# VC8Evrs2.net
KiCad netlist of a schematic drawn in EAGLE
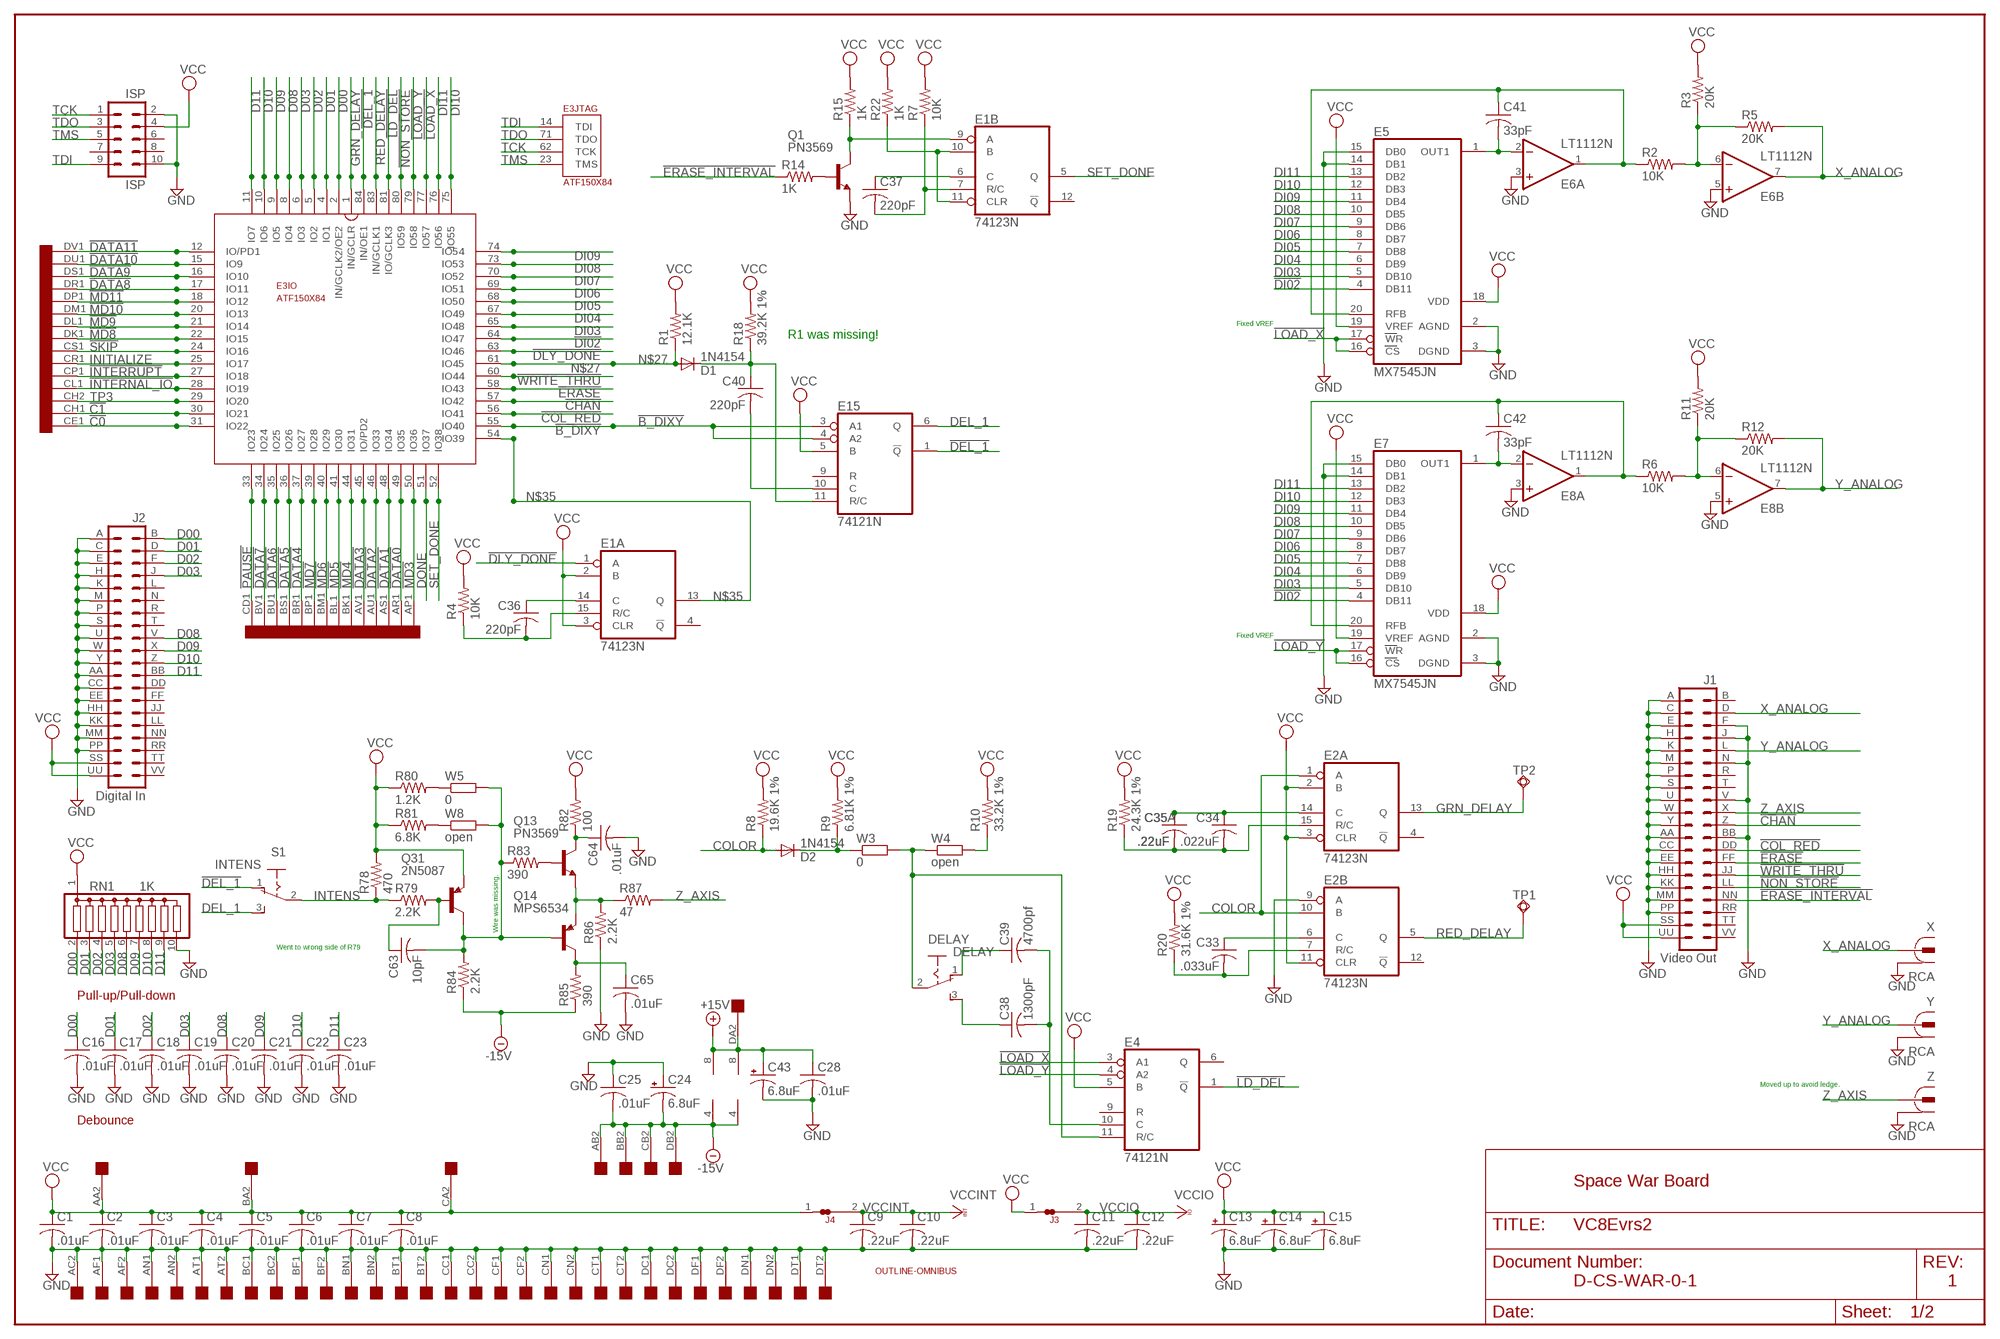
[diagram p0: schematic, sheet 1]

(export (version "E")
  (design (tool "Eeschema 10.0.6"))
  (components
    (comp (ref "C1")
      (value ".01uF")
      (footprint "eagle-import:C063-025X075")
      (libsource (lib "eagle-import") (part "C-US"))
    )
    (comp (ref "C2")
      (value ".01uF")
      (footprint "eagle-import:C063-025X075")
      (libsource (lib "eagle-import") (part "C-US"))
    )
    (comp (ref "C3")
      (value ".01uF")
      (footprint "eagle-import:C063-025X075")
      (libsource (lib "eagle-import") (part "C-US"))
    )
    (comp (ref "C4")
      (value ".01uF")
      (footprint "eagle-import:C063-025X075")
      (libsource (lib "eagle-import") (part "C-US"))
    )
    (comp (ref "C5")
      (value ".01uF")
      (footprint "eagle-import:C063-025X075")
      (libsource (lib "eagle-import") (part "C-US"))
    )
    (comp (ref "C6")
      (value ".01uF")
      (footprint "eagle-import:C063-025X075")
      (libsource (lib "eagle-import") (part "C-US"))
    )
    (comp (ref "C7")
      (value ".01uF")
      (footprint "eagle-import:C063-025X075")
      (libsource (lib "eagle-import") (part "C-US"))
    )
    (comp (ref "C8")
      (value ".01uF")
      (footprint "eagle-import:C063-025X075")
      (libsource (lib "eagle-import") (part "C-US"))
    )
    (comp (ref "C9")
      (value ".22uF")
      (footprint "eagle-import:C063-025X075")
      (libsource (lib "eagle-import") (part "C-US"))
    )
    (comp (ref "C10")
      (value ".22uF")
      (footprint "eagle-import:C063-025X075")
      (libsource (lib "eagle-import") (part "C-US"))
    )
    (comp (ref "C11")
      (value ".22uF")
      (footprint "eagle-import:C063-025X075")
      (libsource (lib "eagle-import") (part "C-US"))
    )
    (comp (ref "C12")
      (value ".22uF")
      (footprint "eagle-import:C063-025X075")
      (libsource (lib "eagle-import") (part "C-US"))
    )
    (comp (ref "C13")
      (value "6.8uF")
      (footprint "eagle-import:E12-8")
      (libsource (lib "eagle-import") (part "CPOL-USE20-8AXIAL"))
    )
    (comp (ref "C14")
      (value "6.8uF")
      (footprint "eagle-import:E12-8")
      (libsource (lib "eagle-import") (part "CPOL-USE20-8AXIAL"))
    )
    (comp (ref "C15")
      (value "6.8uF")
      (footprint "eagle-import:E12-8")
      (libsource (lib "eagle-import") (part "CPOL-USE20-8AXIAL"))
    )
    (comp (ref "C16")
      (value ".01uF")
      (footprint "eagle-import:C063-025X075")
      (libsource (lib "eagle-import") (part "C-US"))
    )
    (comp (ref "C17")
      (value ".01uF")
      (footprint "eagle-import:C063-025X075")
      (libsource (lib "eagle-import") (part "C-US"))
    )
    (comp (ref "C18")
      (value ".01uF")
      (footprint "eagle-import:C063-025X075")
      (libsource (lib "eagle-import") (part "C-US"))
    )
    (comp (ref "C19")
      (value ".01uF")
      (footprint "eagle-import:C063-025X075")
      (libsource (lib "eagle-import") (part "C-US"))
    )
    (comp (ref "C20")
      (value ".01uF")
      (footprint "eagle-import:C063-025X075")
      (libsource (lib "eagle-import") (part "C-US"))
    )
    (comp (ref "C21")
      (value ".01uF")
      (footprint "eagle-import:C063-025X075")
      (libsource (lib "eagle-import") (part "C-US"))
    )
    (comp (ref "C22")
      (value ".01uF")
      (footprint "eagle-import:C063-025X075")
      (libsource (lib "eagle-import") (part "C-US"))
    )
    (comp (ref "C23")
      (value ".01uF")
      (footprint "eagle-import:C063-025X075")
      (libsource (lib "eagle-import") (part "C-US"))
    )
    (comp (ref "C24")
      (value "6.8uF")
      (footprint "eagle-import:E12-8")
      (libsource (lib "eagle-import") (part "CPOL-USE20-8AXIAL"))
    )
    (comp (ref "C25")
      (value ".01uF")
      (footprint "eagle-import:C063-025X075")
      (libsource (lib "eagle-import") (part "C-US"))
    )
    (comp (ref "C28")
      (value ".01uF")
      (footprint "eagle-import:C063-025X075")
      (libsource (lib "eagle-import") (part "C-US"))
    )
    (comp (ref "C33")
      (value ".033uF")
      (footprint "eagle-import:C102-043X133")
      (libsource (lib "eagle-import") (part "C-US102-043X133"))
    )
    (comp (ref "C34")
      (value ".022uF")
      (footprint "eagle-import:C102-043X133")
      (libsource (lib "eagle-import") (part "C-US102-043X133"))
    )
    (comp (ref "C35")
      (value ".22uF")
      (footprint "eagle-import:C050-025X075")
      (libsource (lib "eagle-import") (part "C-US050-025X075"))
    )
    (comp (ref "C35A")
      (value ".22uF")
      (footprint "eagle-import:C102-043X133")
      (libsource (lib "eagle-import") (part "C-US102-043X133"))
    )
    (comp (ref "C36")
      (value "220pF")
      (footprint "eagle-import:C063-025X075")
      (libsource (lib "eagle-import") (part "C-US"))
    )
    (comp (ref "C37")
      (value "220pF")
      (footprint "eagle-import:C063-025X075")
      (libsource (lib "eagle-import") (part "C-US"))
    )
    (comp (ref "C38")
      (value "1300pF")
      (footprint "eagle-import:C150-054X183")
      (libsource (lib "eagle-import") (part "C-US150-054X183"))
    )
    (comp (ref "C39")
      (value "4700pf")
      (footprint "eagle-import:C102-043X133")
      (libsource (lib "eagle-import") (part "C-US102-043X133"))
    )
    (comp (ref "C40")
      (value "220pF")
      (footprint "eagle-import:C063-025X075")
      (libsource (lib "eagle-import") (part "C-US"))
    )
    (comp (ref "C41")
      (value "33pF")
      (footprint "eagle-import:C063-025X075")
      (libsource (lib "eagle-import") (part "C-US"))
    )
    (comp (ref "C42")
      (value "33pF")
      (footprint "eagle-import:C063-025X075")
      (libsource (lib "eagle-import") (part "C-US"))
    )
    (comp (ref "C43")
      (value "6.8uF")
      (footprint "eagle-import:E12-8")
      (libsource (lib "eagle-import") (part "CPOL-USE20-8AXIAL"))
    )
    (comp (ref "C63")
      (value "10pF")
      (footprint "eagle-import:C063-025X075")
      (libsource (lib "eagle-import") (part "C-US"))
    )
    (comp (ref "C64")
      (value ".01uF")
      (footprint "eagle-import:C063-025X075")
      (libsource (lib "eagle-import") (part "C-US"))
    )
    (comp (ref "C65")
      (value ".01uF")
      (footprint "eagle-import:C063-025X075")
      (libsource (lib "eagle-import") (part "C-US"))
    )
    (comp (ref "D1")
      (value "1N4154")
      (footprint "eagle-import:DO35-10")
      (libsource (lib "eagle-import") (part "DIODE-DO35-10"))
    )
    (comp (ref "D2")
      (value "1N4154")
      (footprint "eagle-import:DO35-10")
      (libsource (lib "eagle-import") (part "DIODE-DO35-10"))
    )
    (comp (ref "DELAY")
      (value "DELAY")
      (footprint "eagle-import:M251")
      (libsource (lib "eagle-import") (part "M251"))
    )
    (comp (ref "E1")
      (value "74123N")
      (footprint "eagle-import:DIL16")
      (libsource (lib "eagle-import") (part "74123N"))
    )
    (comp (ref "E2")
      (value "74123N")
      (footprint "eagle-import:DIL16")
      (libsource (lib "eagle-import") (part "74123N"))
    )
    (comp (ref "E3")
      (value "ATF150X84")
      (footprint "eagle-import:S84")
      (libsource (lib "eagle-import") (part "ATF150X84"))
    )
    (comp (ref "E4")
      (value "74121N")
      (footprint "eagle-import:DIL14")
      (libsource (lib "eagle-import") (part "74121N"))
    )
    (comp (ref "E5")
      (value "MX7545JN")
      (footprint "eagle-import:DIL20")
      (fields (field (name "MPN") "MX7545JN+"))
      (libsource (lib "eagle-import") (part "MX7545JN"))
    )
    (comp (ref "E6")
      (value "LT1112N")
      (footprint "eagle-import:DIL08")
      (libsource (lib "eagle-import") (part "1458NLM"))
    )
    (comp (ref "E7")
      (value "MX7545JN")
      (footprint "eagle-import:DIL20")
      (fields (field (name "MPN") "MX7545JN+"))
      (libsource (lib "eagle-import") (part "MX7545JN"))
    )
    (comp (ref "E8")
      (value "LT1112N")
      (footprint "eagle-import:DIL08")
      (libsource (lib "eagle-import") (part "1458NLM"))
    )
    (comp (ref "E15")
      (value "74121N")
      (footprint "eagle-import:DIL14")
      (libsource (lib "eagle-import") (part "74121N"))
    )
    (comp (ref "ISP")
      (value "ISP")
      (footprint "eagle-import:ML10")
      (libsource (lib "eagle-import") (part "ML10"))
    )
    (comp (ref "J1")
      (value "Video Out")
      (footprint "eagle-import:DEC40PINH")
      (libsource (lib "eagle-import") (part "DEC40PINH"))
    )
    (comp (ref "J2")
      (value "Digital In")
      (footprint "eagle-import:DEC40PINH")
      (libsource (lib "eagle-import") (part "DEC40PINH"))
    )
    (comp (ref "J3")
      (value "JUMPER-NC1")
      (footprint "eagle-import:NC1")
      (libsource (lib "eagle-import") (part "JUMPER-NC1"))
    )
    (comp (ref "J4")
      (value "JUMPER-NC1")
      (footprint "eagle-import:NC1")
      (libsource (lib "eagle-import") (part "JUMPER-NC1"))
    )
    (comp (ref "OMNIBUS")
      (value "QUAD")
      (footprint "eagle-import:EDGE-CON8")
      (libsource (lib "eagle-import") (part "QUAD"))
    )
    (comp (ref "Q1")
      (value "PN3569")
      (footprint "eagle-import:TO5")
      (libsource (lib "eagle-import") (part "-NPN-TO5"))
    )
    (comp (ref "Q13")
      (value "PN3569")
      (footprint "eagle-import:TO5")
      (libsource (lib "eagle-import") (part "-NPN-TO5"))
    )
    (comp (ref "Q14")
      (value "MPS6534")
      (footprint "eagle-import:TO5")
      (libsource (lib "eagle-import") (part "-PNP-TO5"))
    )
    (comp (ref "Q31")
      (value "2N5087")
      (footprint "eagle-import:TO5")
      (libsource (lib "eagle-import") (part "-PNP-TO5"))
    )
    (comp (ref "R1")
      (value "12.1K")
      (footprint "eagle-import:0207_15")
      (libsource (lib "eagle-import") (part "R-US_0207/15"))
    )
    (comp (ref "R2")
      (value "10K")
      (footprint "eagle-import:0207_10")
      (libsource (lib "eagle-import") (part "R-US_0207/10"))
    )
    (comp (ref "R3")
      (value "20K")
      (footprint "eagle-import:0207_10")
      (libsource (lib "eagle-import") (part "R-US_0207/10"))
    )
    (comp (ref "R4")
      (value "10K")
      (footprint "eagle-import:0207_10")
      (libsource (lib "eagle-import") (part "R-US_0207/10"))
    )
    (comp (ref "R5")
      (value "20K")
      (footprint "eagle-import:0207_10")
      (libsource (lib "eagle-import") (part "R-US_0207/10"))
    )
    (comp (ref "R6")
      (value "10K")
      (footprint "eagle-import:0207_10")
      (libsource (lib "eagle-import") (part "R-US_0207/10"))
    )
    (comp (ref "R7")
      (value "10K")
      (footprint "eagle-import:0207_10")
      (libsource (lib "eagle-import") (part "R-US_0207/10"))
    )
    (comp (ref "R8")
      (value "19.6K 1%")
      (footprint "eagle-import:0207_15")
      (libsource (lib "eagle-import") (part "R-US_0207/15"))
    )
    (comp (ref "R9")
      (value "6.81K 1%")
      (footprint "eagle-import:0207_15")
      (libsource (lib "eagle-import") (part "R-US_0207/15"))
    )
    (comp (ref "R10")
      (value "33.2K 1%")
      (footprint "eagle-import:0207_15")
      (libsource (lib "eagle-import") (part "R-US_0207/15"))
    )
    (comp (ref "R11")
      (value "20K")
      (footprint "eagle-import:0207_10")
      (libsource (lib "eagle-import") (part "R-US_0207/10"))
    )
    (comp (ref "R12")
      (value "20K")
      (footprint "eagle-import:0207_10")
      (libsource (lib "eagle-import") (part "R-US_0207/10"))
    )
    (comp (ref "R14")
      (value "1K")
      (footprint "eagle-import:0207_10")
      (libsource (lib "eagle-import") (part "R-US_0207/10"))
    )
    (comp (ref "R15")
      (value "1K")
      (footprint "eagle-import:0207_10")
      (libsource (lib "eagle-import") (part "R-US_0207/10"))
    )
    (comp (ref "R18")
      (value "39.2K 1%")
      (footprint "eagle-import:0207_15")
      (libsource (lib "eagle-import") (part "R-US_0207/15"))
    )
    (comp (ref "R19")
      (value "24.3K 1%")
      (footprint "eagle-import:0207_15")
      (libsource (lib "eagle-import") (part "R-US_0207/15"))
    )
    (comp (ref "R20")
      (value "31.6K 1%")
      (footprint "eagle-import:0207_15")
      (libsource (lib "eagle-import") (part "R-US_0207/15"))
    )
    (comp (ref "R22")
      (value "1K")
      (footprint "eagle-import:0207_10")
      (libsource (lib "eagle-import") (part "R-US_0207/10"))
    )
    (comp (ref "R78")
      (value "470")
      (footprint "eagle-import:0207_10")
      (libsource (lib "eagle-import") (part "R-US_0207/10"))
    )
    (comp (ref "R79")
      (value "2.2K")
      (footprint "eagle-import:0207_10")
      (libsource (lib "eagle-import") (part "R-US_0207/10"))
    )
    (comp (ref "R80")
      (value "1.2K")
      (footprint "eagle-import:0207_10")
      (libsource (lib "eagle-import") (part "R-US_0207/10"))
    )
    (comp (ref "R81")
      (value "6.8K")
      (footprint "eagle-import:0207_10")
      (libsource (lib "eagle-import") (part "R-US_0207/10"))
    )
    (comp (ref "R82")
      (value "100")
      (footprint "eagle-import:0207_10")
      (libsource (lib "eagle-import") (part "R-US_0207/10"))
    )
    (comp (ref "R83")
      (value "390")
      (footprint "eagle-import:0207_10")
      (libsource (lib "eagle-import") (part "R-US_0207/10"))
    )
    (comp (ref "R84")
      (value "2.2K")
      (footprint "eagle-import:0207_10")
      (libsource (lib "eagle-import") (part "R-US_0207/10"))
    )
    (comp (ref "R85")
      (value "390")
      (footprint "eagle-import:0207_10")
      (libsource (lib "eagle-import") (part "R-US_0207/10"))
    )
    (comp (ref "R86")
      (value "2.2K")
      (footprint "eagle-import:0207_10")
      (libsource (lib "eagle-import") (part "R-US_0207/10"))
    )
    (comp (ref "R87")
      (value "47")
      (footprint "eagle-import:0207_10")
      (libsource (lib "eagle-import") (part "R-US_0207/10"))
    )
    (comp (ref "RN1")
      (value "1K")
      (footprint "eagle-import:SIL10")
      (libsource (lib "eagle-import") (part "G09R"))
    )
    (comp (ref "S1")
      (value "INTENS")
      (footprint "eagle-import:M251")
      (libsource (lib "eagle-import") (part "M251"))
    )
    (comp (ref "TP1")
      (value "TPSQPAD1-17")
      (footprint "eagle-import:P1-17")
      (libsource (lib "eagle-import") (part "TPSQPAD1-17"))
    )
    (comp (ref "TP2")
      (value "TPSQPAD1-17")
      (footprint "eagle-import:P1-17")
      (libsource (lib "eagle-import") (part "TPSQPAD1-17"))
    )
    (comp (ref "U$1")
      (value "OUTLINE-OMNIBUS")
      (footprint "eagle-import:OMNIBUS")
      (libsource (lib "eagle-import") (part "OUTLINE-OMNIBUS"))
    )
    (comp (ref "W3")
      (value "0")
      (footprint "eagle-import:0207_10")
      (libsource (lib "eagle-import") (part "R-EU_0207/10"))
    )
    (comp (ref "W4")
      (value "open")
      (footprint "eagle-import:0207_10")
      (libsource (lib "eagle-import") (part "R-EU_0207/10"))
    )
    (comp (ref "W5")
      (value "0")
      (footprint "eagle-import:0207_10")
      (libsource (lib "eagle-import") (part "R-EU_0207/10"))
    )
    (comp (ref "W8")
      (value "open")
      (footprint "eagle-import:0207_10")
      (libsource (lib "eagle-import") (part "R-EU_0207/10"))
    )
    (comp (ref "X")
      (value "RCA")
      (footprint "eagle-import:RCA")
      (libsource (lib "eagle-import") (part "RCA"))
    )
    (comp (ref "Y")
      (value "RCA")
      (footprint "eagle-import:RCA")
      (libsource (lib "eagle-import") (part "RCA"))
    )
    (comp (ref "Z")
      (value "RCA")
      (footprint "eagle-import:RCA")
      (libsource (lib "eagle-import") (part "RCA"))
    )
  )
  (nets
    (net (code "1") (name "+15V") (class "Default")
      (node (ref "C28") (pin "1") (pinfunction "1_1") (pintype "passive"))
      (node (ref "C43") (pin "+") (pinfunction "+_+") (pintype "passive"))
      (node (ref "E6") (pin "8") (pinfunction "V+_8") (pintype "power_in"))
      (node (ref "E8") (pin "8") (pinfunction "V+_8") (pintype "power_in"))
      (node (ref "OMNIBUS") (pin "DA2") (pinfunction "1_DA2") (pintype "bidirectional"))
    )
    (net (code "2") (name "-15V") (class "Default")
      (node (ref "C24") (pin "-") (pinfunction "-_-") (pintype "passive"))
      (node (ref "C25") (pin "2") (pinfunction "2_2") (pintype "passive"))
      (node (ref "E6") (pin "4") (pinfunction "V-_4") (pintype "power_in"))
      (node (ref "E8") (pin "4") (pinfunction "V-_4") (pintype "power_in"))
      (node (ref "OMNIBUS") (pin "AB2") (pinfunction "1_AB2") (pintype "bidirectional"))
      (node (ref "OMNIBUS") (pin "BB2") (pinfunction "1_BB2") (pintype "bidirectional"))
      (node (ref "OMNIBUS") (pin "CB2") (pinfunction "1_CB2") (pintype "bidirectional"))
      (node (ref "OMNIBUS") (pin "DB2") (pinfunction "1_DB2") (pintype "bidirectional"))
      (node (ref "R84") (pin "1") (pinfunction "1_1") (pintype "passive"))
      (node (ref "R85") (pin "1") (pinfunction "1_1") (pintype "passive"))
    )
    (net (code "3") (name "COLOR") (class "Default")
      (node (ref "D2") (pin "A") (pinfunction "A_A") (pintype "passive"))
      (node (ref "E2") (pin "1") (pinfunction "A_1") (pintype "input"))
      (node (ref "E2") (pin "10") (pinfunction "B_10") (pintype "input"))
      (node (ref "R8") (pin "1") (pinfunction "1_1") (pintype "passive"))
    )
    (net (code "4") (name "D00") (class "Default")
      (node (ref "C16") (pin "1") (pinfunction "1_1") (pintype "passive"))
      (node (ref "E3") (pin "2") (pinfunction "IN/GCLK2/OE2_2") (pintype "input"))
      (node (ref "J2") (pin "B") (pinfunction "2_B") (pintype "bidirectional"))
      (node (ref "RN1") (pin "2") (pinfunction "2_2") (pintype "passive"))
    )
    (net (code "5") (name "D01") (class "Default")
      (node (ref "C17") (pin "1") (pinfunction "1_1") (pintype "passive"))
      (node (ref "E3") (pin "4") (pinfunction "IO1_4") (pintype "bidirectional"))
      (node (ref "J2") (pin "D") (pinfunction "4_D") (pintype "bidirectional"))
      (node (ref "RN1") (pin "3") (pinfunction "3_3") (pintype "passive"))
    )
    (net (code "6") (name "D02") (class "Default")
      (node (ref "C18") (pin "1") (pinfunction "1_1") (pintype "passive"))
      (node (ref "E3") (pin "5") (pinfunction "IO2_5") (pintype "bidirectional"))
      (node (ref "J2") (pin "F") (pinfunction "6_F") (pintype "bidirectional"))
      (node (ref "RN1") (pin "4") (pinfunction "4_4") (pintype "passive"))
    )
    (net (code "7") (name "D03") (class "Default")
      (node (ref "C19") (pin "1") (pinfunction "1_1") (pintype "passive"))
      (node (ref "E3") (pin "6") (pinfunction "IO3_6") (pintype "bidirectional"))
      (node (ref "J2") (pin "J") (pinfunction "8_J") (pintype "bidirectional"))
      (node (ref "RN1") (pin "5") (pinfunction "5_5") (pintype "passive"))
    )
    (net (code "8") (name "D08") (class "Default")
      (node (ref "C20") (pin "1") (pinfunction "1_1") (pintype "passive"))
      (node (ref "E3") (pin "8") (pinfunction "IO4_8") (pintype "bidirectional"))
      (node (ref "J2") (pin "V") (pinfunction "18_V") (pintype "bidirectional"))
      (node (ref "RN1") (pin "6") (pinfunction "6_6") (pintype "passive"))
    )
    (net (code "9") (name "D09") (class "Default")
      (node (ref "C21") (pin "1") (pinfunction "1_1") (pintype "passive"))
      (node (ref "E3") (pin "9") (pinfunction "IO5_9") (pintype "bidirectional"))
      (node (ref "J2") (pin "X") (pinfunction "20_X") (pintype "bidirectional"))
      (node (ref "RN1") (pin "7") (pinfunction "7_7") (pintype "passive"))
    )
    (net (code "10") (name "D10") (class "Default")
      (node (ref "C22") (pin "1") (pinfunction "1_1") (pintype "passive"))
      (node (ref "E3") (pin "10") (pinfunction "IO6_10") (pintype "bidirectional"))
      (node (ref "J2") (pin "Z") (pinfunction "22_Z") (pintype "bidirectional"))
      (node (ref "RN1") (pin "8") (pinfunction "8_8") (pintype "passive"))
    )
    (net (code "11") (name "D11") (class "Default")
      (node (ref "C23") (pin "1") (pinfunction "1_1") (pintype "passive"))
      (node (ref "E3") (pin "11") (pinfunction "IO7_11") (pintype "bidirectional"))
      (node (ref "J2") (pin "BB") (pinfunction "24_BB") (pintype "bidirectional"))
      (node (ref "RN1") (pin "9") (pinfunction "9_9") (pintype "passive"))
    )
    (net (code "12") (name "DEL_1") (class "Default")
      (node (ref "E15") (pin "6") (pinfunction "Q_6") (pintype "output"))
      (node (ref "S1") (pin "3") (pinfunction "S_3") (pintype "passive"))
    )
    (net (code "13") (name "DI03") (class "Default")
      (node (ref "E3") (pin "65") (pinfunction "IO48_65") (pintype "bidirectional"))
      (node (ref "E5") (pin "5") (pinfunction "DB10_5") (pintype "input"))
      (node (ref "E7") (pin "5") (pinfunction "DB10_5") (pintype "input"))
    )
    (net (code "14") (name "DI04") (class "Default")
      (node (ref "E3") (pin "67") (pinfunction "IO49_67") (pintype "bidirectional"))
      (node (ref "E5") (pin "6") (pinfunction "DB9_6") (pintype "input"))
      (node (ref "E7") (pin "6") (pinfunction "DB9_6") (pintype "input"))
    )
    (net (code "15") (name "DI05") (class "Default")
      (node (ref "E3") (pin "68") (pinfunction "IO50_68") (pintype "bidirectional"))
      (node (ref "E5") (pin "7") (pinfunction "DB8_7") (pintype "input"))
      (node (ref "E7") (pin "7") (pinfunction "DB8_7") (pintype "input"))
    )
    (net (code "16") (name "DI06") (class "Default")
      (node (ref "E3") (pin "69") (pinfunction "IO51_69") (pintype "bidirectional"))
      (node (ref "E5") (pin "8") (pinfunction "DB7_8") (pintype "input"))
      (node (ref "E7") (pin "8") (pinfunction "DB7_8") (pintype "input"))
    )
    (net (code "17") (name "DI07") (class "Default")
      (node (ref "E3") (pin "70") (pinfunction "IO52_70") (pintype "bidirectional"))
      (node (ref "E5") (pin "9") (pinfunction "DB6_9") (pintype "input"))
      (node (ref "E7") (pin "9") (pinfunction "DB6_9") (pintype "input"))
    )
    (net (code "18") (name "DI08") (class "Default")
      (node (ref "E3") (pin "73") (pinfunction "IO53_73") (pintype "bidirectional"))
      (node (ref "E5") (pin "10") (pinfunction "DB5_10") (pintype "input"))
      (node (ref "E7") (pin "10") (pinfunction "DB5_10") (pintype "input"))
    )
    (net (code "19") (name "DI09") (class "Default")
      (node (ref "E3") (pin "74") (pinfunction "IO54_74") (pintype "bidirectional"))
      (node (ref "E5") (pin "11") (pinfunction "DB4_11") (pintype "input"))
      (node (ref "E7") (pin "11") (pinfunction "DB4_11") (pintype "input"))
    )
    (net (code "20") (name "DI10") (class "Default")
      (node (ref "E3") (pin "75") (pinfunction "IO55_75") (pintype "bidirectional"))
      (node (ref "E5") (pin "12") (pinfunction "DB3_12") (pintype "input"))
      (node (ref "E7") (pin "12") (pinfunction "DB3_12") (pintype "input"))
    )
    (net (code "21") (name "DI11") (class "Default")
      (node (ref "E3") (pin "76") (pinfunction "IO56_76") (pintype "bidirectional"))
      (node (ref "E5") (pin "13") (pinfunction "DB2_13") (pintype "input"))
      (node (ref "E7") (pin "13") (pinfunction "DB2_13") (pintype "input"))
    )
    (net (code "22") (name "DONE") (class "Default")
      (node (ref "E3") (pin "51") (pinfunction "IO37_51") (pintype "bidirectional"))
    )
    (net (code "23") (name "GND") (class "Default")
      (node (ref "C1") (pin "2") (pinfunction "2_2") (pintype "passive"))
      (node (ref "C10") (pin "2") (pinfunction "2_2") (pintype "passive"))
      (node (ref "C11") (pin "2") (pinfunction "2_2") (pintype "passive"))
      (node (ref "C12") (pin "2") (pinfunction "2_2") (pintype "passive"))
      (node (ref "C13") (pin "-") (pinfunction "-_-") (pintype "passive"))
      (node (ref "C14") (pin "-") (pinfunction "-_-") (pintype "passive"))
      (node (ref "C15") (pin "-") (pinfunction "-_-") (pintype "passive"))
      (node (ref "C16") (pin "2") (pinfunction "2_2") (pintype "passive"))
      (node (ref "C17") (pin "2") (pinfunction "2_2") (pintype "passive"))
      (node (ref "C18") (pin "2") (pinfunction "2_2") (pintype "passive"))
      (node (ref "C19") (pin "2") (pinfunction "2_2") (pintype "passive"))
      (node (ref "C2") (pin "2") (pinfunction "2_2") (pintype "passive"))
      (node (ref "C20") (pin "2") (pinfunction "2_2") (pintype "passive"))
      (node (ref "C21") (pin "2") (pinfunction "2_2") (pintype "passive"))
      (node (ref "C22") (pin "2") (pinfunction "2_2") (pintype "passive"))
      (node (ref "C23") (pin "2") (pinfunction "2_2") (pintype "passive"))
      (node (ref "C24") (pin "+") (pinfunction "+_+") (pintype "passive"))
      (node (ref "C25") (pin "1") (pinfunction "1_1") (pintype "passive"))
      (node (ref "C28") (pin "2") (pinfunction "2_2") (pintype "passive"))
      (node (ref "C3") (pin "2") (pinfunction "2_2") (pintype "passive"))
      (node (ref "C4") (pin "2") (pinfunction "2_2") (pintype "passive"))
      (node (ref "C43") (pin "-") (pinfunction "-_-") (pintype "passive"))
      (node (ref "C5") (pin "2") (pinfunction "2_2") (pintype "passive"))
      (node (ref "C6") (pin "2") (pinfunction "2_2") (pintype "passive"))
      (node (ref "C64") (pin "2") (pinfunction "2_2") (pintype "passive"))
      (node (ref "C65") (pin "2") (pinfunction "2_2") (pintype "passive"))
      (node (ref "C7") (pin "2") (pinfunction "2_2") (pintype "passive"))
      (node (ref "C8") (pin "2") (pinfunction "2_2") (pintype "passive"))
      (node (ref "C9") (pin "2") (pinfunction "2_2") (pintype "passive"))
      (node (ref "E2") (pin "9") (pinfunction "A_9") (pintype "input"))
      (node (ref "E5") (pin "14") (pinfunction "DB1_14") (pintype "input"))
      (node (ref "E5") (pin "15") (pinfunction "DB0_15") (pintype "input"))
      (node (ref "E5") (pin "2") (pinfunction "AGND_2") (pintype "power_in"))
      (node (ref "E5") (pin "3") (pinfunction "DGND_3") (pintype "power_in"))
      (node (ref "E6") (pin "3") (pinfunction "+IN_3") (pintype "input"))
      (node (ref "E6") (pin "5") (pinfunction "+IN_5") (pintype "input"))
      (node (ref "E7") (pin "14") (pinfunction "DB1_14") (pintype "input"))
      (node (ref "E7") (pin "15") (pinfunction "DB0_15") (pintype "input"))
      (node (ref "E7") (pin "2") (pinfunction "AGND_2") (pintype "power_in"))
      (node (ref "E7") (pin "3") (pinfunction "DGND_3") (pintype "power_in"))
      (node (ref "E8") (pin "3") (pinfunction "+IN_3") (pintype "input"))
      (node (ref "E8") (pin "5") (pinfunction "+IN_5") (pintype "input"))
      (node (ref "ISP") (pin "10") (pinfunction "10_10") (pintype "passive"))
      (node (ref "ISP") (pin "2") (pinfunction "2_2") (pintype "passive"))
      (node (ref "J1") (pin "A") (pinfunction "1_A") (pintype "bidirectional"))
      (node (ref "J1") (pin "AA") (pinfunction "23_AA") (pintype "bidirectional"))
      (node (ref "J1") (pin "BB") (pinfunction "24_BB") (pintype "bidirectional"))
      (node (ref "J1") (pin "C") (pinfunction "3_C") (pintype "bidirectional"))
      (node (ref "J1") (pin "CC") (pinfunction "25_CC") (pintype "bidirectional"))
      (node (ref "J1") (pin "E") (pinfunction "5_E") (pintype "bidirectional"))
      (node (ref "J1") (pin "EE") (pinfunction "27_EE") (pintype "bidirectional"))
      (node (ref "J1") (pin "F") (pinfunction "6_F") (pintype "bidirectional"))
      (node (ref "J1") (pin "H") (pinfunction "7_H") (pintype "bidirectional"))
      (node (ref "J1") (pin "HH") (pinfunction "29_HH") (pintype "bidirectional"))
      (node (ref "J1") (pin "J") (pinfunction "8_J") (pintype "bidirectional"))
      (node (ref "J1") (pin "K") (pinfunction "9_K") (pintype "bidirectional"))
      (node (ref "J1") (pin "KK") (pinfunction "31_KK") (pintype "bidirectional"))
      (node (ref "J1") (pin "M") (pinfunction "11_M") (pintype "bidirectional"))
      (node (ref "J1") (pin "MM") (pinfunction "33_MM") (pintype "bidirectional"))
      (node (ref "J1") (pin "N") (pinfunction "12_N") (pintype "bidirectional"))
      (node (ref "J1") (pin "P") (pinfunction "13_P") (pintype "bidirectional"))
      (node (ref "J1") (pin "PP") (pinfunction "35_PP") (pintype "bidirectional"))
      (node (ref "J1") (pin "S") (pinfunction "15_S") (pintype "bidirectional"))
      (node (ref "J1") (pin "U") (pinfunction "17_U") (pintype "bidirectional"))
      (node (ref "J1") (pin "V") (pinfunction "18_V") (pintype "bidirectional"))
      (node (ref "J1") (pin "W") (pinfunction "19_W") (pintype "bidirectional"))
      (node (ref "J1") (pin "Y") (pinfunction "21_Y") (pintype "bidirectional"))
      (node (ref "J2") (pin "A") (pinfunction "1_A") (pintype "bidirectional"))
      (node (ref "J2") (pin "AA") (pinfunction "23_AA") (pintype "bidirectional"))
      (node (ref "J2") (pin "C") (pinfunction "3_C") (pintype "bidirectional"))
      (node (ref "J2") (pin "CC") (pinfunction "25_CC") (pintype "bidirectional"))
      (node (ref "J2") (pin "E") (pinfunction "5_E") (pintype "bidirectional"))
      (node (ref "J2") (pin "EE") (pinfunction "27_EE") (pintype "bidirectional"))
      (node (ref "J2") (pin "H") (pinfunction "7_H") (pintype "bidirectional"))
      (node (ref "J2") (pin "HH") (pinfunction "29_HH") (pintype "bidirectional"))
      (node (ref "J2") (pin "K") (pinfunction "9_K") (pintype "bidirectional"))
      (node (ref "J2") (pin "KK") (pinfunction "31_KK") (pintype "bidirectional"))
      (node (ref "J2") (pin "M") (pinfunction "11_M") (pintype "bidirectional"))
      (node (ref "J2") (pin "MM") (pinfunction "33_MM") (pintype "bidirectional"))
      (node (ref "J2") (pin "P") (pinfunction "13_P") (pintype "bidirectional"))
      (node (ref "J2") (pin "PP") (pinfunction "35_PP") (pintype "bidirectional"))
      (node (ref "J2") (pin "S") (pinfunction "15_S") (pintype "bidirectional"))
      (node (ref "J2") (pin "U") (pinfunction "17_U") (pintype "bidirectional"))
      (node (ref "J2") (pin "W") (pinfunction "19_W") (pintype "bidirectional"))
      (node (ref "J2") (pin "Y") (pinfunction "21_Y") (pintype "bidirectional"))
      (node (ref "OMNIBUS") (pin "AC2") (pinfunction "1_AC2") (pintype "bidirectional"))
      (node (ref "OMNIBUS") (pin "AF1") (pinfunction "1_AF1") (pintype "bidirectional"))
      (node (ref "OMNIBUS") (pin "AF2") (pinfunction "1_AF2") (pintype "bidirectional"))
      (node (ref "OMNIBUS") (pin "AN1") (pinfunction "1_AN1") (pintype "bidirectional"))
      (node (ref "OMNIBUS") (pin "AN2") (pinfunction "1_AN2") (pintype "bidirectional"))
      (node (ref "OMNIBUS") (pin "AT1") (pinfunction "1_AT1") (pintype "bidirectional"))
      (node (ref "OMNIBUS") (pin "AT2") (pinfunction "1_AT2") (pintype "bidirectional"))
      (node (ref "OMNIBUS") (pin "BC1") (pinfunction "1_BC1") (pintype "bidirectional"))
      (node (ref "OMNIBUS") (pin "BC2") (pinfunction "1_BC2") (pintype "bidirectional"))
      (node (ref "OMNIBUS") (pin "BF1") (pinfunction "1_BF1") (pintype "bidirectional"))
      (node (ref "OMNIBUS") (pin "BF2") (pinfunction "1_BF2") (pintype "bidirectional"))
      (node (ref "OMNIBUS") (pin "BN1") (pinfunction "1_BN1") (pintype "bidirectional"))
      (node (ref "OMNIBUS") (pin "BN2") (pinfunction "1_BN2") (pintype "bidirectional"))
      (node (ref "OMNIBUS") (pin "BT1") (pinfunction "1_BT1") (pintype "bidirectional"))
      (node (ref "OMNIBUS") (pin "BT2") (pinfunction "1_BT2") (pintype "bidirectional"))
      (node (ref "OMNIBUS") (pin "CC1") (pinfunction "1_CC1") (pintype "bidirectional"))
      (node (ref "OMNIBUS") (pin "CC2") (pinfunction "1_CC2") (pintype "bidirectional"))
      (node (ref "OMNIBUS") (pin "CF1") (pinfunction "1_CF1") (pintype "bidirectional"))
      (node (ref "OMNIBUS") (pin "CF2") (pinfunction "1_CF2") (pintype "bidirectional"))
      (node (ref "OMNIBUS") (pin "CN1") (pinfunction "1_CN1") (pintype "bidirectional"))
      (node (ref "OMNIBUS") (pin "CN2") (pinfunction "1_CN2") (pintype "bidirectional"))
      (node (ref "OMNIBUS") (pin "CT1") (pinfunction "1_CT1") (pintype "bidirectional"))
      (node (ref "OMNIBUS") (pin "CT2") (pinfunction "1_CT2") (pintype "bidirectional"))
      (node (ref "OMNIBUS") (pin "DC1") (pinfunction "1_DC1") (pintype "bidirectional"))
      (node (ref "OMNIBUS") (pin "DC2") (pinfunction "1_DC2") (pintype "bidirectional"))
      (node (ref "OMNIBUS") (pin "DF1") (pinfunction "1_DF1") (pintype "bidirectional"))
      (node (ref "OMNIBUS") (pin "DF2") (pinfunction "1_DF2") (pintype "bidirectional"))
      (node (ref "OMNIBUS") (pin "DN1") (pinfunction "1_DN1") (pintype "bidirectional"))
      (node (ref "OMNIBUS") (pin "DN2") (pinfunction "1_DN2") (pintype "bidirectional"))
      (node (ref "OMNIBUS") (pin "DT1") (pinfunction "1_DT1") (pintype "bidirectional"))
      (node (ref "OMNIBUS") (pin "DT2") (pinfunction "1_DT2") (pintype "bidirectional"))
      (node (ref "Q1") (pin "1") (pinfunction "E_1") (pintype "passive"))
      (node (ref "R86") (pin "1") (pinfunction "1_1") (pintype "passive"))
      (node (ref "RN1") (pin "10") (pinfunction "10_10") (pintype "passive"))
      (node (ref "X") (pin "1") (pinfunction "1_1") (pintype "passive"))
      (node (ref "X") (pin "1@1") (pinfunction "1_1@1") (pintype "passive"))
      (node (ref "X") (pin "1@2") (pinfunction "1_1@2") (pintype "passive"))
      (node (ref "Y") (pin "1") (pinfunction "1_1") (pintype "passive"))
      (node (ref "Y") (pin "1@1") (pinfunction "1_1@1") (pintype "passive"))
      (node (ref "Y") (pin "1@2") (pinfunction "1_1@2") (pintype "passive"))
      (node (ref "Z") (pin "1") (pinfunction "1_1") (pintype "passive"))
      (node (ref "Z") (pin "1@1") (pinfunction "1_1@1") (pintype "passive"))
      (node (ref "Z") (pin "1@2") (pinfunction "1_1@2") (pintype "passive"))
    )
    (net (code "24") (name "GRN_DELAY") (class "Default")
      (node (ref "E2") (pin "13") (pinfunction "Q_13") (pintype "output"))
      (node (ref "E3") (pin "1") (pinfunction "IN/GCLR_1") (pintype "input"))
      (node (ref "TP2") (pin "TP") (pinfunction "TP_TP") (pintype "input"))
    )
    (net (code "25") (name "INITIALIZE") (class "Default")
      (node (ref "E3") (pin "25") (pinfunction "IO17_25") (pintype "bidirectional"))
      (node (ref "OMNIBUS") (pin "CR1") (pinfunction "1_CR1") (pintype "bidirectional"))
    )
    (net (code "26") (name "INTENS") (class "Default")
      (node (ref "R78") (pin "1") (pinfunction "1_1") (pintype "passive"))
      (node (ref "R79") (pin "1") (pinfunction "1_1") (pintype "passive"))
      (node (ref "S1") (pin "2") (pinfunction "P_2") (pintype "passive"))
    )
    (net (code "27") (name "N$27") (class "Default")
      (node (ref "D1") (pin "A") (pinfunction "A_A") (pintype "passive"))
      (node (ref "E3") (pin "61") (pinfunction "IO45_61") (pintype "bidirectional"))
      (node (ref "R1") (pin "1") (pinfunction "1_1") (pintype "passive"))
    )
    (net (code "28") (name "N$35") (class "Default")
      (node (ref "E1") (pin "13") (pinfunction "Q_13") (pintype "output"))
      (node (ref "E3") (pin "54") (pinfunction "IO39_54") (pintype "bidirectional"))
    )
    (net (code "29") (name "Net-(D2-PadC)") (class "Default")
      (node (ref "D2") (pin "C") (pinfunction "C_C") (pintype "passive"))
      (node (ref "R9") (pin "1") (pinfunction "1_1") (pintype "passive"))
      (node (ref "W3") (pin "1") (pinfunction "1_1") (pintype "passive"))
    )
    (net (code "30") (name "Net-(DELAY-O)") (class "Default")
      (node (ref "C39") (pin "1") (pinfunction "1_1") (pintype "passive"))
      (node (ref "DELAY") (pin "1") (pinfunction "O_1") (pintype "passive"))
    )
    (net (code "31") (name "Net-(DELAY-P)") (class "Default")
      (node (ref "DELAY") (pin "2") (pinfunction "P_2") (pintype "passive"))
      (node (ref "E4") (pin "11") (pinfunction "R/C_11") (pintype "input"))
      (node (ref "W3") (pin "2") (pinfunction "2_2") (pintype "passive"))
      (node (ref "W4") (pin "1") (pinfunction "1_1") (pintype "passive"))
    )
    (net (code "32") (name "Net-(DELAY-S)") (class "Default")
      (node (ref "C38") (pin "1") (pinfunction "1_1") (pintype "passive"))
      (node (ref "DELAY") (pin "3") (pinfunction "S_3") (pintype "passive"))
    )
    (net (code "33") (name "Net-(E1A-C)") (class "Default")
      (node (ref "C36") (pin "1") (pinfunction "1_1") (pintype "passive"))
      (node (ref "E1") (pin "14") (pinfunction "C_14") (pintype "input"))
    )
    (net (code "34") (name "Net-(E1A-R{slash}C)") (class "Default")
      (node (ref "C36") (pin "2") (pinfunction "2_2") (pintype "passive"))
      (node (ref "E1") (pin "15") (pinfunction "R/C_15") (pintype "input"))
      (node (ref "R4") (pin "1") (pinfunction "1_1") (pintype "passive"))
    )
    (net (code "35") (name "Net-(E1B-A)") (class "Default")
      (node (ref "E1") (pin "9") (pinfunction "A_9") (pintype "input"))
      (node (ref "Q1") (pin "3") (pinfunction "C_3") (pintype "passive"))
      (node (ref "R15") (pin "1") (pinfunction "1_1") (pintype "passive"))
    )
    (net (code "36") (name "Net-(E1B-B)") (class "Default")
      (node (ref "E1") (pin "10") (pinfunction "B_10") (pintype "input"))
      (node (ref "E1") (pin "11") (pinfunction "CLR_11") (pintype "input"))
      (node (ref "R22") (pin "1") (pinfunction "1_1") (pintype "passive"))
    )
    (net (code "37") (name "Net-(E1B-C)") (class "Default")
      (node (ref "C37") (pin "1") (pinfunction "1_1") (pintype "passive"))
      (node (ref "E1") (pin "6") (pinfunction "C_6") (pintype "input"))
    )
    (net (code "38") (name "Net-(E1B-R{slash}C)") (class "Default")
      (node (ref "C37") (pin "2") (pinfunction "2_2") (pintype "passive"))
      (node (ref "E1") (pin "7") (pinfunction "R/C_7") (pintype "input"))
      (node (ref "R7") (pin "1") (pinfunction "1_1") (pintype "passive"))
    )
    (net (code "39") (name "Net-(E2A-C)") (class "Default")
      (node (ref "C34") (pin "1") (pinfunction "1_1") (pintype "passive"))
      (node (ref "C35") (pin "1") (pinfunction "1_1") (pintype "passive"))
      (node (ref "C35A") (pin "1") (pinfunction "1_1") (pintype "passive"))
      (node (ref "E2") (pin "14") (pinfunction "C_14") (pintype "input"))
    )
    (net (code "40") (name "Net-(E2A-R{slash}C)") (class "Default")
      (node (ref "C34") (pin "2") (pinfunction "2_2") (pintype "passive"))
      (node (ref "C35") (pin "2") (pinfunction "2_2") (pintype "passive"))
      (node (ref "C35A") (pin "2") (pinfunction "2_2") (pintype "passive"))
      (node (ref "E2") (pin "15") (pinfunction "R/C_15") (pintype "input"))
      (node (ref "R19") (pin "1") (pinfunction "1_1") (pintype "passive"))
    )
    (net (code "41") (name "Net-(E2B-C)") (class "Default")
      (node (ref "C33") (pin "1") (pinfunction "1_1") (pintype "passive"))
      (node (ref "E2") (pin "6") (pinfunction "C_6") (pintype "input"))
    )
    (net (code "42") (name "Net-(E2B-R{slash}C)") (class "Default")
      (node (ref "C33") (pin "2") (pinfunction "2_2") (pintype "passive"))
      (node (ref "E2") (pin "7") (pinfunction "R/C_7") (pintype "input"))
      (node (ref "R20") (pin "1") (pinfunction "1_1") (pintype "passive"))
    )
    (net (code "43") (name "Net-(E4A-C)") (class "Default")
      (node (ref "C38") (pin "2") (pinfunction "2_2") (pintype "passive"))
      (node (ref "C39") (pin "2") (pinfunction "2_2") (pintype "passive"))
      (node (ref "E4") (pin "10") (pinfunction "C_10") (pintype "input"))
    )
    (net (code "44") (name "Net-(E5-OUT1)") (class "Default")
      (node (ref "C41") (pin "2") (pinfunction "2_2") (pintype "passive"))
      (node (ref "E5") (pin "1") (pinfunction "OUT1_1") (pintype "output"))
      (node (ref "E6") (pin "2") (pinfunction "-IN_2") (pintype "input"))
    )
    (net (code "45") (name "Net-(E5-RFB)") (class "Default")
      (node (ref "C41") (pin "1") (pinfunction "1_1") (pintype "passive"))
      (node (ref "E5") (pin "20") (pinfunction "RFB_20") (pintype "input"))
      (node (ref "E6") (pin "1") (pinfunction "OUT_1") (pintype "output"))
      (node (ref "R2") (pin "1") (pinfunction "1_1") (pintype "passive"))
    )
    (net (code "46") (name "Net-(E6B--IN)") (class "Default")
      (node (ref "E6") (pin "6") (pinfunction "-IN_6") (pintype "input"))
      (node (ref "R2") (pin "2") (pinfunction "2_2") (pintype "passive"))
      (node (ref "R3") (pin "1") (pinfunction "1_1") (pintype "passive"))
      (node (ref "R5") (pin "1") (pinfunction "1_1") (pintype "passive"))
    )
    (net (code "47") (name "Net-(E7-OUT1)") (class "Default")
      (node (ref "C42") (pin "2") (pinfunction "2_2") (pintype "passive"))
      (node (ref "E7") (pin "1") (pinfunction "OUT1_1") (pintype "output"))
      (node (ref "E8") (pin "2") (pinfunction "-IN_2") (pintype "input"))
    )
    (net (code "48") (name "Net-(E7-RFB)") (class "Default")
      (node (ref "C42") (pin "1") (pinfunction "1_1") (pintype "passive"))
      (node (ref "E7") (pin "20") (pinfunction "RFB_20") (pintype "input"))
      (node (ref "E8") (pin "1") (pinfunction "OUT_1") (pintype "output"))
      (node (ref "R6") (pin "1") (pinfunction "1_1") (pintype "passive"))
    )
    (net (code "49") (name "Net-(E8B--IN)") (class "Default")
      (node (ref "E8") (pin "6") (pinfunction "-IN_6") (pintype "input"))
      (node (ref "R11") (pin "1") (pinfunction "1_1") (pintype "passive"))
      (node (ref "R12") (pin "1") (pinfunction "1_1") (pintype "passive"))
      (node (ref "R6") (pin "2") (pinfunction "2_2") (pintype "passive"))
    )
    (net (code "50") (name "Net-(E15A-C)") (class "Default")
      (node (ref "C40") (pin "2") (pinfunction "2_2") (pintype "passive"))
      (node (ref "E15") (pin "10") (pinfunction "C_10") (pintype "input"))
    )
    (net (code "51") (name "Net-(E15A-R{slash}C)") (class "Default")
      (node (ref "C40") (pin "1") (pinfunction "1_1") (pintype "passive"))
      (node (ref "D1") (pin "C") (pinfunction "C_C") (pintype "passive"))
      (node (ref "E15") (pin "11") (pinfunction "R/C_11") (pintype "input"))
      (node (ref "R18") (pin "1") (pinfunction "1_1") (pintype "passive"))
    )
    (net (code "52") (name "Net-(Q1-B)") (class "Default")
      (node (ref "Q1") (pin "2") (pinfunction "B_2") (pintype "passive"))
      (node (ref "R14") (pin "2") (pinfunction "2_2") (pintype "passive"))
    )
    (net (code "53") (name "Net-(Q13-B)") (class "Default")
      (node (ref "Q13") (pin "2") (pinfunction "B_2") (pintype "passive"))
      (node (ref "R83") (pin "2") (pinfunction "2_2") (pintype "passive"))
    )
    (net (code "54") (name "Net-(Q13-C)") (class "Default")
      (node (ref "C64") (pin "1") (pinfunction "1_1") (pintype "passive"))
      (node (ref "Q13") (pin "3") (pinfunction "C_3") (pintype "passive"))
      (node (ref "R82") (pin "1") (pinfunction "1_1") (pintype "passive"))
    )
    (net (code "55") (name "Net-(Q13-E)") (class "Default")
      (node (ref "Q13") (pin "1") (pinfunction "E_1") (pintype "passive"))
      (node (ref "Q14") (pin "1") (pinfunction "E_1") (pintype "passive"))
      (node (ref "R86") (pin "2") (pinfunction "2_2") (pintype "passive"))
      (node (ref "R87") (pin "1") (pinfunction "1_1") (pintype "passive"))
    )
    (net (code "56") (name "Net-(Q14-B)") (class "Default")
      (node (ref "C63") (pin "2") (pinfunction "2_2") (pintype "passive"))
      (node (ref "Q14") (pin "2") (pinfunction "B_2") (pintype "passive"))
      (node (ref "Q31") (pin "3") (pinfunction "C_3") (pintype "passive"))
      (node (ref "R83") (pin "1") (pinfunction "1_1") (pintype "passive"))
      (node (ref "R84") (pin "2") (pinfunction "2_2") (pintype "passive"))
      (node (ref "W5") (pin "2") (pinfunction "2_2") (pintype "passive"))
      (node (ref "W8") (pin "2") (pinfunction "2_2") (pintype "passive"))
    )
    (net (code "57") (name "Net-(Q14-C)") (class "Default")
      (node (ref "C65") (pin "1") (pinfunction "1_1") (pintype "passive"))
      (node (ref "Q14") (pin "3") (pinfunction "C_3") (pintype "passive"))
      (node (ref "R85") (pin "2") (pinfunction "2_2") (pintype "passive"))
    )
    (net (code "58") (name "Net-(Q31-B)") (class "Default")
      (node (ref "C63") (pin "1") (pinfunction "1_1") (pintype "passive"))
      (node (ref "Q31") (pin "2") (pinfunction "B_2") (pintype "passive"))
      (node (ref "R79") (pin "2") (pinfunction "2_2") (pintype "passive"))
    )
    (net (code "59") (name "Net-(R10-Pad1)") (class "Default")
      (node (ref "R10") (pin "1") (pinfunction "1_1") (pintype "passive"))
      (node (ref "W4") (pin "2") (pinfunction "2_2") (pintype "passive"))
    )
    (net (code "60") (name "Net-(R80-Pad2)") (class "Default")
      (node (ref "R80") (pin "2") (pinfunction "2_2") (pintype "passive"))
      (node (ref "W5") (pin "1") (pinfunction "1_1") (pintype "passive"))
    )
    (net (code "61") (name "Net-(R81-Pad2)") (class "Default")
      (node (ref "R81") (pin "2") (pinfunction "2_2") (pintype "passive"))
      (node (ref "W8") (pin "1") (pinfunction "1_1") (pintype "passive"))
    )
    (net (code "62") (name "RED_DELAY") (class "Default")
      (node (ref "E2") (pin "5") (pinfunction "Q_5") (pintype "output"))
      (node (ref "E3") (pin "83") (pinfunction "IN/GCLK1_83") (pintype "input"))
      (node (ref "TP1") (pin "TP") (pinfunction "TP_TP") (pintype "input"))
    )
    (net (code "63") (name "SET_DONE") (class "Default")
      (node (ref "E1") (pin "5") (pinfunction "Q_5") (pintype "output"))
      (node (ref "E3") (pin "52") (pinfunction "IO38_52") (pintype "bidirectional"))
    )
    (net (code "64") (name "TCK") (class "Default")
      (node (ref "E3") (pin "62") (pinfunction "TCK_62") (pintype "bidirectional"))
      (node (ref "ISP") (pin "1") (pinfunction "1_1") (pintype "passive"))
    )
    (net (code "65") (name "TDI") (class "Default")
      (node (ref "E3") (pin "14") (pinfunction "TDI_14") (pintype "bidirectional"))
      (node (ref "ISP") (pin "9") (pinfunction "9_9") (pintype "passive"))
    )
    (net (code "66") (name "TDO") (class "Default")
      (node (ref "E3") (pin "71") (pinfunction "TDO_71") (pintype "bidirectional"))
      (node (ref "ISP") (pin "3") (pinfunction "3_3") (pintype "passive"))
    )
    (net (code "67") (name "TMS") (class "Default")
      (node (ref "E3") (pin "23") (pinfunction "TMS_23") (pintype "bidirectional"))
      (node (ref "ISP") (pin "5") (pinfunction "5_5") (pintype "passive"))
    )
    (net (code "68") (name "TP3") (class "Default")
      (node (ref "E3") (pin "29") (pinfunction "IO20_29") (pintype "bidirectional"))
      (node (ref "OMNIBUS") (pin "CH2") (pinfunction "1_CH2") (pintype "bidirectional"))
    )
    (net (code "69") (name "VCC") (class "Default")
      (node (ref "C1") (pin "1") (pinfunction "1_1") (pintype "passive"))
      (node (ref "C13") (pin "+") (pinfunction "+_+") (pintype "passive"))
      (node (ref "C14") (pin "+") (pinfunction "+_+") (pintype "passive"))
      (node (ref "C15") (pin "+") (pinfunction "+_+") (pintype "passive"))
      (node (ref "C2") (pin "1") (pinfunction "1_1") (pintype "passive"))
      (node (ref "C3") (pin "1") (pinfunction "1_1") (pintype "passive"))
      (node (ref "C4") (pin "1") (pinfunction "1_1") (pintype "passive"))
      (node (ref "C5") (pin "1") (pinfunction "1_1") (pintype "passive"))
      (node (ref "C6") (pin "1") (pinfunction "1_1") (pintype "passive"))
      (node (ref "C7") (pin "1") (pinfunction "1_1") (pintype "passive"))
      (node (ref "C8") (pin "1") (pinfunction "1_1") (pintype "passive"))
      (node (ref "E1") (pin "2") (pinfunction "B_2") (pintype "input"))
      (node (ref "E1") (pin "3") (pinfunction "CLR_3") (pintype "input"))
      (node (ref "E15") (pin "5") (pinfunction "B_5") (pintype "input"))
      (node (ref "E2") (pin "11") (pinfunction "CLR_11") (pintype "input"))
      (node (ref "E2") (pin "2") (pinfunction "B_2") (pintype "input"))
      (node (ref "E2") (pin "3") (pinfunction "CLR_3") (pintype "input"))
      (node (ref "E4") (pin "5") (pinfunction "B_5") (pintype "input"))
      (node (ref "E5") (pin "18") (pinfunction "VDD_18") (pintype "power_in"))
      (node (ref "E5") (pin "19") (pinfunction "VREF_19") (pintype "input"))
      (node (ref "E7") (pin "18") (pinfunction "VDD_18") (pintype "power_in"))
      (node (ref "E7") (pin "19") (pinfunction "VREF_19") (pintype "input"))
      (node (ref "ISP") (pin "4") (pinfunction "4_4") (pintype "passive"))
      (node (ref "J1") (pin "SS") (pinfunction "37_SS") (pintype "bidirectional"))
      (node (ref "J1") (pin "UU") (pinfunction "39_UU") (pintype "bidirectional"))
      (node (ref "J2") (pin "SS") (pinfunction "37_SS") (pintype "bidirectional"))
      (node (ref "J2") (pin "UU") (pinfunction "39_UU") (pintype "bidirectional"))
      (node (ref "J3") (pin "1") (pinfunction "1_1") (pintype "bidirectional"))
      (node (ref "J4") (pin "1") (pinfunction "1_1") (pintype "bidirectional"))
      (node (ref "OMNIBUS") (pin "AA2") (pinfunction "1_AA2") (pintype "bidirectional"))
      (node (ref "OMNIBUS") (pin "BA2") (pinfunction "1_BA2") (pintype "bidirectional"))
      (node (ref "OMNIBUS") (pin "CA2") (pinfunction "1_CA2") (pintype "bidirectional"))
      (node (ref "Q31") (pin "1") (pinfunction "E_1") (pintype "passive"))
      (node (ref "R1") (pin "2") (pinfunction "2_2") (pintype "passive"))
      (node (ref "R10") (pin "2") (pinfunction "2_2") (pintype "passive"))
      (node (ref "R11") (pin "2") (pinfunction "2_2") (pintype "passive"))
      (node (ref "R15") (pin "2") (pinfunction "2_2") (pintype "passive"))
      (node (ref "R18") (pin "2") (pinfunction "2_2") (pintype "passive"))
      (node (ref "R19") (pin "2") (pinfunction "2_2") (pintype "passive"))
      (node (ref "R20") (pin "2") (pinfunction "2_2") (pintype "passive"))
      (node (ref "R22") (pin "2") (pinfunction "2_2") (pintype "passive"))
      (node (ref "R3") (pin "2") (pinfunction "2_2") (pintype "passive"))
      (node (ref "R4") (pin "2") (pinfunction "2_2") (pintype "passive"))
      (node (ref "R7") (pin "2") (pinfunction "2_2") (pintype "passive"))
      (node (ref "R78") (pin "2") (pinfunction "2_2") (pintype "passive"))
      (node (ref "R8") (pin "2") (pinfunction "2_2") (pintype "passive"))
      (node (ref "R80") (pin "1") (pinfunction "1_1") (pintype "passive"))
      (node (ref "R81") (pin "1") (pinfunction "1_1") (pintype "passive"))
      (node (ref "R82") (pin "2") (pinfunction "2_2") (pintype "passive"))
      (node (ref "R9") (pin "2") (pinfunction "2_2") (pintype "passive"))
      (node (ref "RN1") (pin "1") (pinfunction "1_1") (pintype "passive"))
    )
    (net (code "70") (name "VCCINT") (class "Default")
      (node (ref "C10") (pin "1") (pinfunction "1_1") (pintype "passive"))
      (node (ref "C9") (pin "1") (pinfunction "1_1") (pintype "passive"))
      (node (ref "J4") (pin "2") (pinfunction "2_2") (pintype "bidirectional"))
    )
    (net (code "71") (name "VCCIO") (class "Default")
      (node (ref "C11") (pin "1") (pinfunction "1_1") (pintype "passive"))
      (node (ref "C12") (pin "1") (pinfunction "1_1") (pintype "passive"))
      (node (ref "J3") (pin "2") (pinfunction "2_2") (pintype "bidirectional"))
    )
    (net (code "72") (name "X_ANALOG") (class "Default")
      (node (ref "E6") (pin "7") (pinfunction "OUT_7") (pintype "output"))
      (node (ref "J1") (pin "D") (pinfunction "4_D") (pintype "bidirectional"))
      (node (ref "R5") (pin "2") (pinfunction "2_2") (pintype "passive"))
      (node (ref "X") (pin "2") (pinfunction "2_2") (pintype "passive"))
    )
    (net (code "73") (name "Y_ANALOG") (class "Default")
      (node (ref "E8") (pin "7") (pinfunction "OUT_7") (pintype "output"))
      (node (ref "J1") (pin "L") (pinfunction "10_L") (pintype "bidirectional"))
      (node (ref "R12") (pin "2") (pinfunction "2_2") (pintype "passive"))
      (node (ref "Y") (pin "2") (pinfunction "2_2") (pintype "passive"))
    )
    (net (code "74") (name "Z_AXIS") (class "Default")
      (node (ref "J1") (pin "X") (pinfunction "20_X") (pintype "bidirectional"))
      (node (ref "R87") (pin "2") (pinfunction "2_2") (pintype "passive"))
      (node (ref "Z") (pin "2") (pinfunction "2_2") (pintype "passive"))
    )
    (net (code "75") (name "unconnected-(E1A-~{Q}-Pad4)") (class "Default")
      (node (ref "E1") (pin "4") (pinfunction "~{Q}_4") (pintype "output"))
    )
    (net (code "76") (name "unconnected-(E1B-~{Q}-Pad12)") (class "Default")
      (node (ref "E1") (pin "12") (pinfunction "~{Q}_12") (pintype "output"))
    )
    (net (code "77") (name "unconnected-(E2A-~{Q}-Pad4)") (class "Default")
      (node (ref "E2") (pin "4") (pinfunction "~{Q}_4") (pintype "output"))
    )
    (net (code "78") (name "unconnected-(E2B-~{Q}-Pad12)") (class "Default")
      (node (ref "E2") (pin "12") (pinfunction "~{Q}_12") (pintype "output"))
    )
    (net (code "79") (name "unconnected-(E4A-Q-Pad6)") (class "Default")
      (node (ref "E4") (pin "6") (pinfunction "Q_6") (pintype "output"))
    )
    (net (code "80") (name "unconnected-(E4A-R-Pad9)") (class "Default")
      (node (ref "E4") (pin "9") (pinfunction "R_9") (pintype "input"))
    )
    (net (code "81") (name "unconnected-(E15A-R-Pad9)") (class "Default")
      (node (ref "E15") (pin "9") (pinfunction "R_9") (pintype "input"))
    )
    (net (code "82") (name "unconnected-(ISP-Pad6)") (class "Default")
      (node (ref "ISP") (pin "6") (pinfunction "6_6") (pintype "passive"))
    )
    (net (code "83") (name "unconnected-(ISP-Pad7)") (class "Default")
      (node (ref "ISP") (pin "7") (pinfunction "7_7") (pintype "passive"))
    )
    (net (code "84") (name "unconnected-(ISP-Pad8)") (class "Default")
      (node (ref "ISP") (pin "8") (pinfunction "8_8") (pintype "passive"))
    )
    (net (code "85") (name "unconnected-(J1-2-PadB)") (class "Default")
      (node (ref "J1") (pin "B") (pinfunction "2_B") (pintype "bidirectional"))
    )
    (net (code "86") (name "unconnected-(J1-14-PadR)") (class "Default")
      (node (ref "J1") (pin "R") (pinfunction "14_R") (pintype "bidirectional"))
    )
    (net (code "87") (name "unconnected-(J1-16-PadT)") (class "Default")
      (node (ref "J1") (pin "T") (pinfunction "16_T") (pintype "bidirectional"))
    )
    (net (code "88") (name "unconnected-(J1-36-PadRR)") (class "Default")
      (node (ref "J1") (pin "RR") (pinfunction "36_RR") (pintype "bidirectional"))
    )
    (net (code "89") (name "unconnected-(J1-38-PadTT)") (class "Default")
      (node (ref "J1") (pin "TT") (pinfunction "38_TT") (pintype "bidirectional"))
    )
    (net (code "90") (name "unconnected-(J1-40-PadVV)") (class "Default")
      (node (ref "J1") (pin "VV") (pinfunction "40_VV") (pintype "bidirectional"))
    )
    (net (code "91") (name "unconnected-(J2-10-PadL)") (class "Default")
      (node (ref "J2") (pin "L") (pinfunction "10_L") (pintype "bidirectional"))
    )
    (net (code "92") (name "unconnected-(J2-12-PadN)") (class "Default")
      (node (ref "J2") (pin "N") (pinfunction "12_N") (pintype "bidirectional"))
    )
    (net (code "93") (name "unconnected-(J2-14-PadR)") (class "Default")
      (node (ref "J2") (pin "R") (pinfunction "14_R") (pintype "bidirectional"))
    )
    (net (code "94") (name "unconnected-(J2-16-PadT)") (class "Default")
      (node (ref "J2") (pin "T") (pinfunction "16_T") (pintype "bidirectional"))
    )
    (net (code "95") (name "unconnected-(J2-26-PadDD)") (class "Default")
      (node (ref "J2") (pin "DD") (pinfunction "26_DD") (pintype "bidirectional"))
    )
    (net (code "96") (name "unconnected-(J2-28-PadFF)") (class "Default")
      (node (ref "J2") (pin "FF") (pinfunction "28_FF") (pintype "bidirectional"))
    )
    (net (code "97") (name "unconnected-(J2-30-PadJJ)") (class "Default")
      (node (ref "J2") (pin "JJ") (pinfunction "30_JJ") (pintype "bidirectional"))
    )
    (net (code "98") (name "unconnected-(J2-32-PadLL)") (class "Default")
      (node (ref "J2") (pin "LL") (pinfunction "32_LL") (pintype "bidirectional"))
    )
    (net (code "99") (name "unconnected-(J2-34-PadNN)") (class "Default")
      (node (ref "J2") (pin "NN") (pinfunction "34_NN") (pintype "bidirectional"))
    )
    (net (code "100") (name "unconnected-(J2-36-PadRR)") (class "Default")
      (node (ref "J2") (pin "RR") (pinfunction "36_RR") (pintype "bidirectional"))
    )
    (net (code "101") (name "unconnected-(J2-38-PadTT)") (class "Default")
      (node (ref "J2") (pin "TT") (pinfunction "38_TT") (pintype "bidirectional"))
    )
    (net (code "102") (name "unconnected-(J2-40-PadVV)") (class "Default")
      (node (ref "J2") (pin "VV") (pinfunction "40_VV") (pintype "bidirectional"))
    )
    (net (code "103") (name "~{B_DIXY}") (class "Default")
      (node (ref "E15") (pin "3") (pinfunction "A1_3") (pintype "input"))
      (node (ref "E15") (pin "4") (pinfunction "A2_4") (pintype "input"))
      (node (ref "E3") (pin "55") (pinfunction "IO40_55") (pintype "bidirectional"))
    )
    (net (code "104") (name "~{C0}") (class "Default")
      (node (ref "E3") (pin "31") (pinfunction "IO22_31") (pintype "bidirectional"))
      (node (ref "OMNIBUS") (pin "CE1") (pinfunction "1_CE1") (pintype "bidirectional"))
    )
    (net (code "105") (name "~{C1}") (class "Default")
      (node (ref "E3") (pin "30") (pinfunction "IO21_30") (pintype "bidirectional"))
      (node (ref "OMNIBUS") (pin "CH1") (pinfunction "1_CH1") (pintype "bidirectional"))
    )
    (net (code "106") (name "~{CHAN}") (class "Default")
      (node (ref "E3") (pin "57") (pinfunction "IO42_57") (pintype "bidirectional"))
      (node (ref "J1") (pin "Z") (pinfunction "22_Z") (pintype "bidirectional"))
    )
    (net (code "107") (name "~{COL_RED}") (class "Default")
      (node (ref "E3") (pin "56") (pinfunction "IO41_56") (pintype "bidirectional"))
      (node (ref "J1") (pin "DD") (pinfunction "26_DD") (pintype "bidirectional"))
    )
    (net (code "108") (name "~{DATA0}") (class "Default")
      (node (ref "E3") (pin "49") (pinfunction "IO35_49") (pintype "bidirectional"))
      (node (ref "OMNIBUS") (pin "AR1") (pinfunction "1_AR1") (pintype "bidirectional"))
    )
    (net (code "109") (name "~{DATA1}") (class "Default")
      (node (ref "E3") (pin "48") (pinfunction "IO34_48") (pintype "bidirectional"))
      (node (ref "OMNIBUS") (pin "AS1") (pinfunction "1_AS1") (pintype "bidirectional"))
    )
    (net (code "110") (name "~{DATA2}") (class "Default")
      (node (ref "E3") (pin "46") (pinfunction "IO33_46") (pintype "bidirectional"))
      (node (ref "OMNIBUS") (pin "AU1") (pinfunction "1_AU1") (pintype "bidirectional"))
    )
    (net (code "111") (name "~{DATA3}") (class "Default")
      (node (ref "E3") (pin "45") (pinfunction "IO/PD2_45") (pintype "bidirectional"))
      (node (ref "OMNIBUS") (pin "AV1") (pinfunction "1_AV1") (pintype "bidirectional"))
    )
    (net (code "112") (name "~{DATA4}") (class "Default")
      (node (ref "E3") (pin "37") (pinfunction "IO27_37") (pintype "bidirectional"))
      (node (ref "OMNIBUS") (pin "BR1") (pinfunction "1_BR1") (pintype "bidirectional"))
    )
    (net (code "113") (name "~{DATA5}") (class "Default")
      (node (ref "E3") (pin "36") (pinfunction "IO26_36") (pintype "bidirectional"))
      (node (ref "OMNIBUS") (pin "BS1") (pinfunction "1_BS1") (pintype "bidirectional"))
    )
    (net (code "114") (name "~{DATA6}") (class "Default")
      (node (ref "E3") (pin "35") (pinfunction "IO25_35") (pintype "bidirectional"))
      (node (ref "OMNIBUS") (pin "BU1") (pinfunction "1_BU1") (pintype "bidirectional"))
    )
    (net (code "115") (name "~{DATA7}") (class "Default")
      (node (ref "E3") (pin "34") (pinfunction "IO24_34") (pintype "bidirectional"))
      (node (ref "OMNIBUS") (pin "BV1") (pinfunction "1_BV1") (pintype "bidirectional"))
    )
    (net (code "116") (name "~{DATA8}") (class "Default")
      (node (ref "E3") (pin "17") (pinfunction "IO11_17") (pintype "bidirectional"))
      (node (ref "OMNIBUS") (pin "DR1") (pinfunction "1_DR1") (pintype "bidirectional"))
    )
    (net (code "117") (name "~{DATA9}") (class "Default")
      (node (ref "E3") (pin "16") (pinfunction "IO10_16") (pintype "bidirectional"))
      (node (ref "OMNIBUS") (pin "DS1") (pinfunction "1_DS1") (pintype "bidirectional"))
    )
    (net (code "118") (name "~{DATA10}") (class "Default")
      (node (ref "E3") (pin "15") (pinfunction "IO9_15") (pintype "bidirectional"))
      (node (ref "OMNIBUS") (pin "DU1") (pinfunction "1_DU1") (pintype "bidirectional"))
    )
    (net (code "119") (name "~{DATA11}") (class "Default")
      (node (ref "E3") (pin "12") (pinfunction "IO/PD1_12") (pintype "bidirectional"))
      (node (ref "OMNIBUS") (pin "DV1") (pinfunction "1_DV1") (pintype "bidirectional"))
    )
    (net (code "120") (name "~{DEL_1}") (class "Default")
      (node (ref "E15") (pin "1") (pinfunction "~{Q}_1") (pintype "output"))
      (node (ref "E3") (pin "84") (pinfunction "IN/OE1_84") (pintype "input"))
      (node (ref "S1") (pin "1") (pinfunction "O_1") (pintype "passive"))
    )
    (net (code "121") (name "~{DI02}") (class "Default")
      (node (ref "E3") (pin "64") (pinfunction "IO47_64") (pintype "bidirectional"))
      (node (ref "E5") (pin "4") (pinfunction "DB11_4") (pintype "input"))
      (node (ref "E7") (pin "4") (pinfunction "DB11_4") (pintype "input"))
    )
    (net (code "122") (name "~{DLY_DONE}") (class "Default")
      (node (ref "E1") (pin "1") (pinfunction "A_1") (pintype "input"))
      (node (ref "E3") (pin "63") (pinfunction "IO46_63") (pintype "bidirectional"))
    )
    (net (code "123") (name "~{ERASE_INTERVAL}") (class "Default")
      (node (ref "J1") (pin "NN") (pinfunction "34_NN") (pintype "bidirectional"))
      (node (ref "R14") (pin "1") (pinfunction "1_1") (pintype "passive"))
    )
    (net (code "124") (name "~{ERASE}") (class "Default")
      (node (ref "E3") (pin "58") (pinfunction "IO43_58") (pintype "bidirectional"))
      (node (ref "J1") (pin "FF") (pinfunction "28_FF") (pintype "bidirectional"))
    )
    (net (code "125") (name "~{INTERNAL_IO}") (class "Default")
      (node (ref "E3") (pin "28") (pinfunction "IO19_28") (pintype "bidirectional"))
      (node (ref "OMNIBUS") (pin "CL1") (pinfunction "1_CL1") (pintype "bidirectional"))
    )
    (net (code "126") (name "~{INTERRUPT}") (class "Default")
      (node (ref "E3") (pin "27") (pinfunction "IO18_27") (pintype "bidirectional"))
      (node (ref "OMNIBUS") (pin "CP1") (pinfunction "1_CP1") (pintype "bidirectional"))
    )
    (net (code "127") (name "~{LD_DEL}") (class "Default")
      (node (ref "E3") (pin "81") (pinfunction "IO/GCLK3_81") (pintype "bidirectional"))
      (node (ref "E4") (pin "1") (pinfunction "~{Q}_1") (pintype "output"))
    )
    (net (code "128") (name "~{LOAD_X}") (class "Default")
      (node (ref "E3") (pin "77") (pinfunction "IO57_77") (pintype "bidirectional"))
      (node (ref "E4") (pin "3") (pinfunction "A1_3") (pintype "input"))
      (node (ref "E5") (pin "16") (pinfunction "CS_16") (pintype "input"))
      (node (ref "E5") (pin "17") (pinfunction "WR_17") (pintype "input"))
    )
    (net (code "129") (name "~{LOAD_Y}") (class "Default")
      (node (ref "E3") (pin "79") (pinfunction "IO58_79") (pintype "bidirectional"))
      (node (ref "E4") (pin "4") (pinfunction "A2_4") (pintype "input"))
      (node (ref "E7") (pin "16") (pinfunction "CS_16") (pintype "input"))
      (node (ref "E7") (pin "17") (pinfunction "WR_17") (pintype "input"))
    )
    (net (code "130") (name "~{MD3}") (class "Default")
      (node (ref "E3") (pin "50") (pinfunction "IO36_50") (pintype "bidirectional"))
      (node (ref "OMNIBUS") (pin "AP1") (pinfunction "1_AP1") (pintype "bidirectional"))
    )
    (net (code "131") (name "~{MD4}") (class "Default")
      (node (ref "E3") (pin "44") (pinfunction "IO31_44") (pintype "bidirectional"))
      (node (ref "OMNIBUS") (pin "BK1") (pinfunction "1_BK1") (pintype "bidirectional"))
    )
    (net (code "132") (name "~{MD5}") (class "Default")
      (node (ref "E3") (pin "41") (pinfunction "IO30_41") (pintype "bidirectional"))
      (node (ref "OMNIBUS") (pin "BL1") (pinfunction "1_BL1") (pintype "bidirectional"))
    )
    (net (code "133") (name "~{MD6}") (class "Default")
      (node (ref "E3") (pin "40") (pinfunction "IO29_40") (pintype "bidirectional"))
      (node (ref "OMNIBUS") (pin "BM1") (pinfunction "1_BM1") (pintype "bidirectional"))
    )
    (net (code "134") (name "~{MD7}") (class "Default")
      (node (ref "E3") (pin "39") (pinfunction "IO28_39") (pintype "bidirectional"))
      (node (ref "OMNIBUS") (pin "BP1") (pinfunction "1_BP1") (pintype "bidirectional"))
    )
    (net (code "135") (name "~{MD8}") (class "Default")
      (node (ref "E3") (pin "22") (pinfunction "IO15_22") (pintype "bidirectional"))
      (node (ref "OMNIBUS") (pin "DK1") (pinfunction "1_DK1") (pintype "bidirectional"))
    )
    (net (code "136") (name "~{MD9}") (class "Default")
      (node (ref "E3") (pin "21") (pinfunction "IO14_21") (pintype "bidirectional"))
      (node (ref "OMNIBUS") (pin "DL1") (pinfunction "1_DL1") (pintype "bidirectional"))
    )
    (net (code "137") (name "~{MD10}") (class "Default")
      (node (ref "E3") (pin "20") (pinfunction "IO13_20") (pintype "bidirectional"))
      (node (ref "OMNIBUS") (pin "DM1") (pinfunction "1_DM1") (pintype "bidirectional"))
    )
    (net (code "138") (name "~{MD11}") (class "Default")
      (node (ref "E3") (pin "18") (pinfunction "IO12_18") (pintype "bidirectional"))
      (node (ref "OMNIBUS") (pin "DP1") (pinfunction "1_DP1") (pintype "bidirectional"))
    )
    (net (code "139") (name "~{NON_STORE}") (class "Default")
      (node (ref "E3") (pin "80") (pinfunction "IO59_80") (pintype "bidirectional"))
      (node (ref "J1") (pin "LL") (pinfunction "32_LL") (pintype "bidirectional"))
    )
    (net (code "140") (name "~{PAUSE}") (class "Default")
      (node (ref "E3") (pin "33") (pinfunction "IO23_33") (pintype "bidirectional"))
      (node (ref "OMNIBUS") (pin "CD1") (pinfunction "1_CD1") (pintype "bidirectional"))
    )
    (net (code "141") (name "~{SKIP}") (class "Default")
      (node (ref "E3") (pin "24") (pinfunction "IO16_24") (pintype "bidirectional"))
      (node (ref "OMNIBUS") (pin "CS1") (pinfunction "1_CS1") (pintype "bidirectional"))
    )
    (net (code "142") (name "~{WRITE_THRU}") (class "Default")
      (node (ref "E3") (pin "60") (pinfunction "IO44_60") (pintype "bidirectional"))
      (node (ref "J1") (pin "JJ") (pinfunction "30_JJ") (pintype "bidirectional"))
    )
  )
)
